# Accumulator_Indicator_22-12.net
KiCad netlist of a schematic drawn in Altium Designer
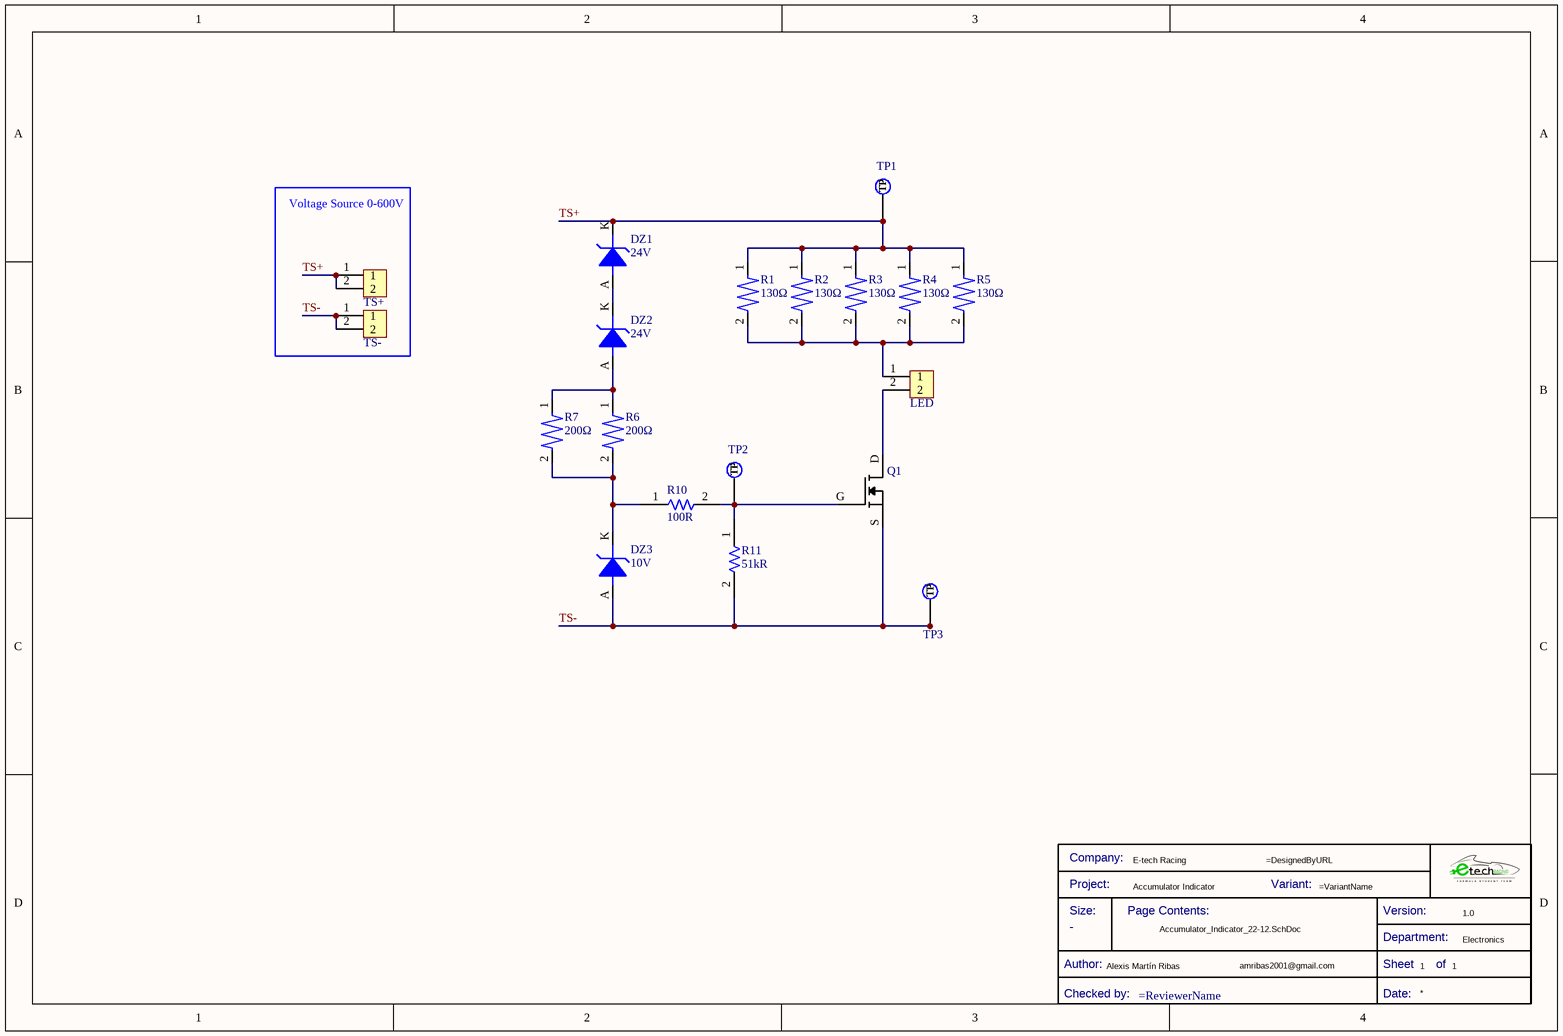
[diagram p0: Accumulator_Indicator_22-12.SchDoc]

(export (version "E")
  (design (tool "Eeschema 10.0.6"))
  (components
    (comp (ref "*")
      (value "Title Block_template")
      (description "Standard Title Block")
      (fields
        (field (name "SIZE") "-")
        (field (name ".CREATOR") "GP")
        (field (name ".PCBCHECK") "GP")
        (field (name ".SCHCHECK") "GP")
      )
      (libsource (lib "e-Tech_Racing") (part "Title Block_template"))
    )
    (comp (ref "DZ1")
      (value "24V")
      (footprint "DZ_24V_STD")
      (description "BZX55C24")
      (libsource (lib "AM_Schlib") (part "DZ_24V_STD"))
    )
    (comp (ref "DZ2")
      (value "24V")
      (footprint "DZ_24V_STD")
      (description "BZX55C24")
      (libsource (lib "AM_Schlib") (part "DZ_24V_STD"))
    )
    (comp (ref "DZ3")
      (value "10V")
      (footprint "DZ_24V_BZT52H-A10-Q")
      (libsource (lib "AM_Schlib") (part "DZ_24V_BZT52H-A10-Q"))
    )
    (comp (ref "LED")
      (value "436500215")
      (footprint "J_MicroFit_2x1")
      (description "Header 1 Row Vertical Polarizing Peg 2 Pin SMT/Glow Wire Compatible Tin Plate")
      (libsource (lib "Electromechanical") (part "J_MicroFit_2x1"))
    )
    (comp (ref "Q1")
      (value "D2PAK type-A")
      (footprint "MOSFET-N-D2PAK")
      (description "STB36N60M6")
      (libsource (lib "AM_Schlib") (part "MOSFET-N-D2PAK"))
    )
    (comp (ref "R1")
      (value "130Ω")
      (footprint "R130K_3W413")
      (libsource (lib "AM_Schlib") (part "R130K_3W413"))
    )
    (comp (ref "R2")
      (value "130Ω")
      (footprint "R130K_3W413")
      (libsource (lib "AM_Schlib") (part "R130K_3W413"))
    )
    (comp (ref "R3")
      (value "130Ω")
      (footprint "R130K_3W413")
      (libsource (lib "AM_Schlib") (part "R130K_3W413"))
    )
    (comp (ref "R4")
      (value "130Ω")
      (footprint "R130K_3W413")
      (libsource (lib "AM_Schlib") (part "R130K_3W413"))
    )
    (comp (ref "R5")
      (value "130Ω")
      (footprint "R130K_3W413")
      (libsource (lib "AM_Schlib") (part "R130K_3W413"))
    )
    (comp (ref "R6") (value "200Ω") (footprint "R200K_2W") (libsource (lib "AM_Schlib") (part "R200K_2W")))
    (comp (ref "R7") (value "200Ω") (footprint "R200K_2W") (libsource (lib "AM_Schlib") (part "R200K_2W")))
    (comp (ref "R10")
      (value "CRG1206F100R")
      (footprint "R1206FTK-W")
      (description "Res Thick Film 1206 100 Ohm 1% 0.25W(1/4W) ±200ppm/C Pad SMD T/R")
      (fields
        (field (name "MANUFACTURER") "TE Connectivity")
        (field (name "TOLERANCE") "1%")
        (field (name "RESISTANCE") "100R")
        (field (name ".CREATOR") "AC")
      )
      (libsource (lib "Passives") (part "R100-1206FTK"))
    )
    (comp (ref "R11")
      (value "CRCW120610K0FKEA")
      (footprint "R1206FTK-W")
      (description "Res Thick Film 1206 51K Ohm 1% 1/4W ±100ppm/°C Molded SMD SMD Punched Carrier T/R")
      (fields
        (field (name "MANUFACTURER") "Panasonic")
        (field (name "MANUFACTURER PART NUMBER") "ERJ-S08F5102V")
        (field (name "RESISTANCE") "51kR")
        (field (name ".CREATOR") "DO")
      )
      (libsource (lib "Passives") (part "R51k-1206FTK"))
    )
    (comp (ref "TP1")
      (value "TestPoint")
      (footprint "TestPoint")
      (description "Test Point 1x1 mm")
      (fields (field (name ".CREATOR") "GP") (field (name ".PCBCHECK") "GP") (field (name ".SCHCHECK") "GP"))
      (libsource (lib "e-Tech_Racing") (part "TestPoint"))
    )
    (comp (ref "TP2")
      (value "TestPoint")
      (footprint "TestPoint")
      (description "Test Point 1x1 mm")
      (fields (field (name ".CREATOR") "GP") (field (name ".PCBCHECK") "GP") (field (name ".SCHCHECK") "GP"))
      (libsource (lib "e-Tech_Racing") (part "TestPoint"))
    )
    (comp (ref "TP3")
      (value "TestPoint")
      (footprint "TestPoint")
      (description "Test Point 1x1 mm")
      (fields (field (name ".CREATOR") "GP") (field (name ".PCBCHECK") "GP") (field (name ".SCHCHECK") "GP"))
      (libsource (lib "e-Tech_Racing") (part "TestPoint"))
    )
    (comp (ref "TS+")
      (value "436500215")
      (footprint "J_MicroFit_2x1")
      (description "Header 1 Row Vertical Polarizing Peg 2 Pin SMT/Glow Wire Compatible Tin Plate")
      (libsource (lib "Electromechanical") (part "J_MicroFit_2x1"))
    )
    (comp (ref "TS-")
      (value "436500215")
      (footprint "J_MicroFit_2x1")
      (description "Header 1 Row Vertical Polarizing Peg 2 Pin SMT/Glow Wire Compatible Tin Plate")
      (libsource (lib "Electromechanical") (part "J_MicroFit_2x1"))
    )
  )
  (nets
    (net (code "1") (name "/TS+") (class "Default")
      (node (ref "DZ1") (pin "K") (pinfunction "K_K") (pintype "passive"))
      (node (ref "R1") (pin "1") (pinfunction "1_1") (pintype "passive"))
      (node (ref "R2") (pin "1") (pinfunction "1_1") (pintype "passive"))
      (node (ref "R3") (pin "1") (pinfunction "1_1") (pintype "passive"))
      (node (ref "R4") (pin "1") (pinfunction "1_1") (pintype "passive"))
      (node (ref "R5") (pin "1") (pinfunction "1_1") (pintype "passive"))
      (node (ref "TP1") (pin "1") (pinfunction "TP_1") (pintype "passive"))
      (node (ref "TS+") (pin "1") (pinfunction "1_1") (pintype "passive"))
      (node (ref "TS+") (pin "2") (pinfunction "2_2") (pintype "passive"))
    )
    (net (code "2") (name "/TS-") (class "Default")
      (node (ref "DZ3") (pin "A") (pinfunction "A_A") (pintype "passive"))
      (node (ref "Q1") (pin "S") (pinfunction "S_S") (pintype "passive"))
      (node (ref "R11") (pin "2") (pinfunction "2_2") (pintype "passive"))
      (node (ref "TP3") (pin "1") (pinfunction "TP_1") (pintype "passive"))
      (node (ref "TS-") (pin "1") (pinfunction "1_1") (pintype "passive"))
      (node (ref "TS-") (pin "2") (pinfunction "2_2") (pintype "passive"))
    )
    (net (code "3") (name "Net-(DZ1-PadA)") (class "Default")
      (node (ref "DZ1") (pin "A") (pinfunction "A_A") (pintype "passive"))
      (node (ref "DZ2") (pin "K") (pinfunction "K_K") (pintype "passive"))
    )
    (net (code "4") (name "Net-(DZ2-PadA)") (class "Default")
      (node (ref "DZ2") (pin "A") (pinfunction "A_A") (pintype "passive"))
      (node (ref "R6") (pin "1") (pinfunction "1_1") (pintype "passive"))
      (node (ref "R7") (pin "1") (pinfunction "1_1") (pintype "passive"))
    )
    (net (code "5") (name "Net-(DZ3-PadK)") (class "Default")
      (node (ref "DZ3") (pin "K") (pinfunction "K_K") (pintype "passive"))
      (node (ref "R10") (pin "1") (pinfunction "1_1") (pintype "passive"))
      (node (ref "R6") (pin "2") (pinfunction "2_2") (pintype "passive"))
      (node (ref "R7") (pin "2") (pinfunction "2_2") (pintype "passive"))
    )
    (net (code "6") (name "Net-(LED-Pad1)") (class "Default")
      (node (ref "LED") (pin "1") (pinfunction "1_1") (pintype "passive"))
      (node (ref "R1") (pin "2") (pinfunction "2_2") (pintype "passive"))
      (node (ref "R2") (pin "2") (pinfunction "2_2") (pintype "passive"))
      (node (ref "R3") (pin "2") (pinfunction "2_2") (pintype "passive"))
      (node (ref "R4") (pin "2") (pinfunction "2_2") (pintype "passive"))
      (node (ref "R5") (pin "2") (pinfunction "2_2") (pintype "passive"))
    )
    (net (code "7") (name "Net-(LED-Pad2)") (class "Default")
      (node (ref "LED") (pin "2") (pinfunction "2_2") (pintype "passive"))
      (node (ref "Q1") (pin "D") (pinfunction "D_D") (pintype "passive"))
    )
    (net (code "8") (name "Net-(TP2-TP)") (class "Default")
      (node (ref "Q1") (pin "G") (pinfunction "G_G") (pintype "passive"))
      (node (ref "R10") (pin "2") (pinfunction "2_2") (pintype "passive"))
      (node (ref "R11") (pin "1") (pinfunction "1_1") (pintype "passive"))
      (node (ref "TP2") (pin "1") (pinfunction "TP_1") (pintype "passive"))
    )
  )
)
